# Peripheral_Connections.net
KiCad netlist of a schematic drawn in Altium Designer
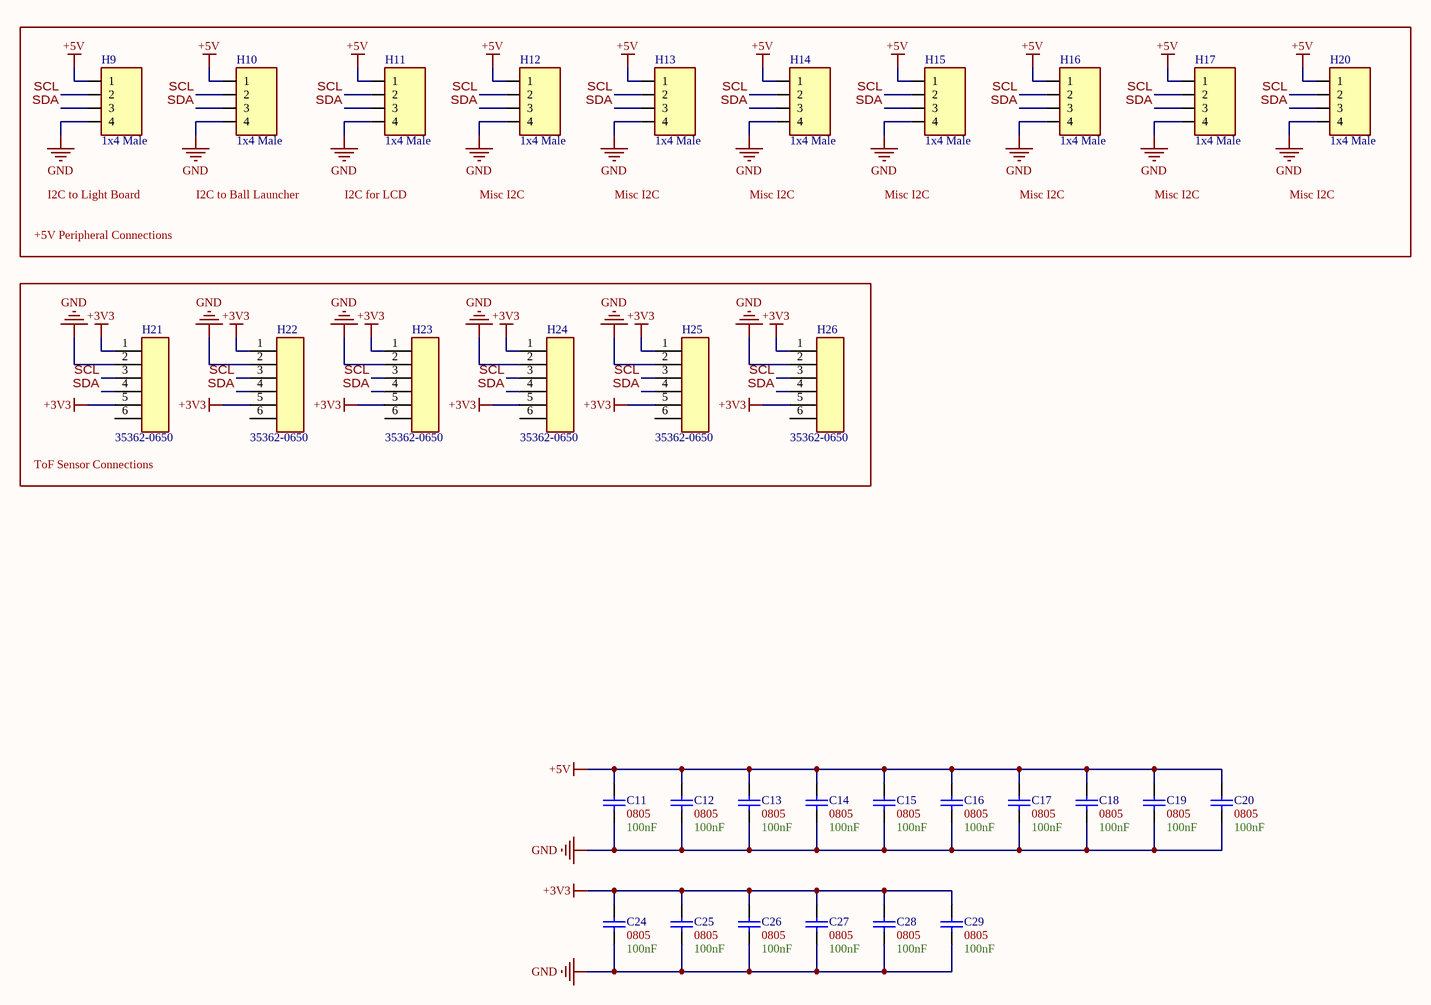
[diagram p0: Peripheral Connections.SchDoc]

(export (version "E")
  (design (tool "Eeschema 10.0.6"))
  (components
    (comp (ref "C11")
      (value "SMD Nonpolarized")
      (footprint "[Cap] SMD 0805")
      (fields (field (name "SIZE PACKAGE") "0805") (field (name "CAPACITANCE") "100nF"))
      (libsource (lib "RADM Components") (part "[Cap] SMD Nonpolarized"))
    )
    (comp (ref "C12")
      (value "SMD Nonpolarized")
      (footprint "[Cap] SMD 0805")
      (fields (field (name "SIZE PACKAGE") "0805") (field (name "CAPACITANCE") "100nF"))
      (libsource (lib "RADM Components") (part "[Cap] SMD Nonpolarized"))
    )
    (comp (ref "C13")
      (value "SMD Nonpolarized")
      (footprint "[Cap] SMD 0805")
      (fields (field (name "SIZE PACKAGE") "0805") (field (name "CAPACITANCE") "100nF"))
      (libsource (lib "RADM Components") (part "[Cap] SMD Nonpolarized"))
    )
    (comp (ref "C14")
      (value "SMD Nonpolarized")
      (footprint "[Cap] SMD 0805")
      (fields (field (name "SIZE PACKAGE") "0805") (field (name "CAPACITANCE") "100nF"))
      (libsource (lib "RADM Components") (part "[Cap] SMD Nonpolarized"))
    )
    (comp (ref "C15")
      (value "SMD Nonpolarized")
      (footprint "[Cap] SMD 0805")
      (fields (field (name "SIZE PACKAGE") "0805") (field (name "CAPACITANCE") "100nF"))
      (libsource (lib "RADM Components") (part "[Cap] SMD Nonpolarized"))
    )
    (comp (ref "C16")
      (value "SMD Nonpolarized")
      (footprint "[Cap] SMD 0805")
      (fields (field (name "SIZE PACKAGE") "0805") (field (name "CAPACITANCE") "100nF"))
      (libsource (lib "RADM Components") (part "[Cap] SMD Nonpolarized"))
    )
    (comp (ref "C17")
      (value "SMD Nonpolarized")
      (footprint "[Cap] SMD 0805")
      (fields (field (name "SIZE PACKAGE") "0805") (field (name "CAPACITANCE") "100nF"))
      (libsource (lib "RADM Components") (part "[Cap] SMD Nonpolarized"))
    )
    (comp (ref "C18")
      (value "SMD Nonpolarized")
      (footprint "[Cap] SMD 0805")
      (fields (field (name "SIZE PACKAGE") "0805") (field (name "CAPACITANCE") "100nF"))
      (libsource (lib "RADM Components") (part "[Cap] SMD Nonpolarized"))
    )
    (comp (ref "C19")
      (value "SMD Nonpolarized")
      (footprint "[Cap] SMD 0805")
      (fields (field (name "SIZE PACKAGE") "0805") (field (name "CAPACITANCE") "100nF"))
      (libsource (lib "RADM Components") (part "[Cap] SMD Nonpolarized"))
    )
    (comp (ref "C20")
      (value "SMD Nonpolarized")
      (footprint "[Cap] SMD 0805")
      (fields (field (name "SIZE PACKAGE") "0805") (field (name "CAPACITANCE") "100nF"))
      (libsource (lib "RADM Components") (part "[Cap] SMD Nonpolarized"))
    )
    (comp (ref "C24")
      (value "SMD Nonpolarized")
      (footprint "[Cap] SMD 0805")
      (fields (field (name "SIZE PACKAGE") "0805") (field (name "CAPACITANCE") "100nF"))
      (libsource (lib "RADM Components") (part "[Cap] SMD Nonpolarized"))
    )
    (comp (ref "C25")
      (value "SMD Nonpolarized")
      (footprint "[Cap] SMD 0805")
      (fields (field (name "SIZE PACKAGE") "0805") (field (name "CAPACITANCE") "100nF"))
      (libsource (lib "RADM Components") (part "[Cap] SMD Nonpolarized"))
    )
    (comp (ref "C26")
      (value "SMD Nonpolarized")
      (footprint "[Cap] SMD 0805")
      (fields (field (name "SIZE PACKAGE") "0805") (field (name "CAPACITANCE") "100nF"))
      (libsource (lib "RADM Components") (part "[Cap] SMD Nonpolarized"))
    )
    (comp (ref "C27")
      (value "SMD Nonpolarized")
      (footprint "[Cap] SMD 0805")
      (fields (field (name "SIZE PACKAGE") "0805") (field (name "CAPACITANCE") "100nF"))
      (libsource (lib "RADM Components") (part "[Cap] SMD Nonpolarized"))
    )
    (comp (ref "C28")
      (value "SMD Nonpolarized")
      (footprint "[Cap] SMD 0805")
      (fields (field (name "SIZE PACKAGE") "0805") (field (name "CAPACITANCE") "100nF"))
      (libsource (lib "RADM Components") (part "[Cap] SMD Nonpolarized"))
    )
    (comp (ref "C29")
      (value "SMD Nonpolarized")
      (footprint "[Cap] SMD 0805")
      (fields (field (name "SIZE PACKAGE") "0805") (field (name "CAPACITANCE") "100nF"))
      (libsource (lib "RADM Components") (part "[Cap] SMD Nonpolarized"))
    )
    (comp (ref "H9")
      (value "1x4 Male")
      (footprint "[Header] Shrouded 1x4 Male")
      (description "70543-0003\r\nMates with 0050579404")
      (libsource (lib "RADM Connectors") (part "[Header] Shrouded 1x4 Male"))
    )
    (comp (ref "H10")
      (value "1x4 Male")
      (footprint "[Header] Shrouded 1x4 Male")
      (description "70543-0003\r\nMates with 0050579404")
      (libsource (lib "RADM Connectors") (part "[Header] Shrouded 1x4 Male"))
    )
    (comp (ref "H11")
      (value "1x4 Male")
      (footprint "[Header] Shrouded 1x4 Male")
      (description "70543-0003\r\nMates with 0050579404")
      (libsource (lib "RADM Connectors") (part "[Header] Shrouded 1x4 Male"))
    )
    (comp (ref "H12")
      (value "1x4 Male")
      (footprint "[Header] Shrouded 1x4 Male")
      (description "70543-0003\r\nMates with 0050579404")
      (libsource (lib "RADM Connectors") (part "[Header] Shrouded 1x4 Male"))
    )
    (comp (ref "H13")
      (value "1x4 Male")
      (footprint "[Header] Shrouded 1x4 Male")
      (description "70543-0003\r\nMates with 0050579404")
      (libsource (lib "RADM Connectors") (part "[Header] Shrouded 1x4 Male"))
    )
    (comp (ref "H14")
      (value "1x4 Male")
      (footprint "[Header] Shrouded 1x4 Male")
      (description "70543-0003\r\nMates with 0050579404")
      (libsource (lib "RADM Connectors") (part "[Header] Shrouded 1x4 Male"))
    )
    (comp (ref "H15")
      (value "1x4 Male")
      (footprint "[Header] Shrouded 1x4 Male")
      (description "70543-0003\r\nMates with 0050579404")
      (libsource (lib "RADM Connectors") (part "[Header] Shrouded 1x4 Male"))
    )
    (comp (ref "H16")
      (value "1x4 Male")
      (footprint "[Header] Shrouded 1x4 Male")
      (description "70543-0003\r\nMates with 0050579404")
      (libsource (lib "RADM Connectors") (part "[Header] Shrouded 1x4 Male"))
    )
    (comp (ref "H17")
      (value "1x4 Male")
      (footprint "[Header] Shrouded 1x4 Male")
      (description "70543-0003\r\nMates with 0050579404")
      (libsource (lib "RADM Connectors") (part "[Header] Shrouded 1x4 Male"))
    )
    (comp (ref "H20")
      (value "1x4 Male")
      (footprint "[Header] Shrouded 1x4 Male")
      (description "70543-0003\r\nMates with 0050579404")
      (libsource (lib "RADM Connectors") (part "[Header] Shrouded 1x4 Male"))
    )
    (comp (ref "H21")
      (value "35362-0650")
      (footprint "[Sherlock] 6pin")
      (description "2.00mm pitch")
      (libsource (lib "RADM Connectors") (part "[Sherlock] 6pin"))
    )
    (comp (ref "H22")
      (value "35362-0650")
      (footprint "[Sherlock] 6pin")
      (description "2.00mm pitch")
      (libsource (lib "RADM Connectors") (part "[Sherlock] 6pin"))
    )
    (comp (ref "H23")
      (value "35362-0650")
      (footprint "[Sherlock] 6pin")
      (description "2.00mm pitch")
      (libsource (lib "RADM Connectors") (part "[Sherlock] 6pin"))
    )
    (comp (ref "H24")
      (value "35362-0650")
      (footprint "[Sherlock] 6pin")
      (description "2.00mm pitch")
      (libsource (lib "RADM Connectors") (part "[Sherlock] 6pin"))
    )
    (comp (ref "H25")
      (value "35362-0650")
      (footprint "[Sherlock] 6pin")
      (description "2.00mm pitch")
      (libsource (lib "RADM Connectors") (part "[Sherlock] 6pin"))
    )
    (comp (ref "H26")
      (value "35362-0650")
      (footprint "[Sherlock] 6pin")
      (description "2.00mm pitch")
      (libsource (lib "RADM Connectors") (part "[Sherlock] 6pin"))
    )
  )
  (nets
    (net (code "1") (name "+3V3") (class "Default")
      (node (ref "C24") (pin "2") (pinfunction "2_2") (pintype "passive"))
      (node (ref "C25") (pin "2") (pinfunction "2_2") (pintype "passive"))
      (node (ref "C26") (pin "2") (pinfunction "2_2") (pintype "passive"))
      (node (ref "C27") (pin "2") (pinfunction "2_2") (pintype "passive"))
      (node (ref "C28") (pin "2") (pinfunction "2_2") (pintype "passive"))
      (node (ref "C29") (pin "2") (pinfunction "2_2") (pintype "passive"))
      (node (ref "H21") (pin "1") (pinfunction "1_1") (pintype "passive"))
      (node (ref "H21") (pin "5") (pinfunction "5_5") (pintype "passive"))
      (node (ref "H22") (pin "1") (pinfunction "1_1") (pintype "passive"))
      (node (ref "H22") (pin "5") (pinfunction "5_5") (pintype "passive"))
      (node (ref "H23") (pin "1") (pinfunction "1_1") (pintype "passive"))
      (node (ref "H23") (pin "5") (pinfunction "5_5") (pintype "passive"))
      (node (ref "H24") (pin "1") (pinfunction "1_1") (pintype "passive"))
      (node (ref "H24") (pin "5") (pinfunction "5_5") (pintype "passive"))
      (node (ref "H25") (pin "1") (pinfunction "1_1") (pintype "passive"))
      (node (ref "H25") (pin "5") (pinfunction "5_5") (pintype "passive"))
      (node (ref "H26") (pin "1") (pinfunction "1_1") (pintype "passive"))
      (node (ref "H26") (pin "5") (pinfunction "5_5") (pintype "passive"))
    )
    (net (code "2") (name "+5V") (class "Default")
      (node (ref "C11") (pin "2") (pinfunction "2_2") (pintype "passive"))
      (node (ref "C12") (pin "2") (pinfunction "2_2") (pintype "passive"))
      (node (ref "C13") (pin "2") (pinfunction "2_2") (pintype "passive"))
      (node (ref "C14") (pin "2") (pinfunction "2_2") (pintype "passive"))
      (node (ref "C15") (pin "2") (pinfunction "2_2") (pintype "passive"))
      (node (ref "C16") (pin "2") (pinfunction "2_2") (pintype "passive"))
      (node (ref "C17") (pin "2") (pinfunction "2_2") (pintype "passive"))
      (node (ref "C18") (pin "2") (pinfunction "2_2") (pintype "passive"))
      (node (ref "C19") (pin "2") (pinfunction "2_2") (pintype "passive"))
      (node (ref "C20") (pin "2") (pinfunction "2_2") (pintype "passive"))
      (node (ref "H10") (pin "1") (pinfunction "1_1") (pintype "passive"))
      (node (ref "H11") (pin "1") (pinfunction "1_1") (pintype "passive"))
      (node (ref "H12") (pin "1") (pinfunction "1_1") (pintype "passive"))
      (node (ref "H13") (pin "1") (pinfunction "1_1") (pintype "passive"))
      (node (ref "H14") (pin "1") (pinfunction "1_1") (pintype "passive"))
      (node (ref "H15") (pin "1") (pinfunction "1_1") (pintype "passive"))
      (node (ref "H16") (pin "1") (pinfunction "1_1") (pintype "passive"))
      (node (ref "H17") (pin "1") (pinfunction "1_1") (pintype "passive"))
      (node (ref "H20") (pin "1") (pinfunction "1_1") (pintype "passive"))
      (node (ref "H9") (pin "1") (pinfunction "1_1") (pintype "passive"))
    )
    (net (code "3") (name "/SCL") (class "Default")
      (node (ref "H10") (pin "2") (pinfunction "2_2") (pintype "passive"))
      (node (ref "H11") (pin "2") (pinfunction "2_2") (pintype "passive"))
      (node (ref "H12") (pin "2") (pinfunction "2_2") (pintype "passive"))
      (node (ref "H13") (pin "2") (pinfunction "2_2") (pintype "passive"))
      (node (ref "H14") (pin "2") (pinfunction "2_2") (pintype "passive"))
      (node (ref "H15") (pin "2") (pinfunction "2_2") (pintype "passive"))
      (node (ref "H16") (pin "2") (pinfunction "2_2") (pintype "passive"))
      (node (ref "H17") (pin "2") (pinfunction "2_2") (pintype "passive"))
      (node (ref "H20") (pin "2") (pinfunction "2_2") (pintype "passive"))
      (node (ref "H21") (pin "3") (pinfunction "3_3") (pintype "passive"))
      (node (ref "H22") (pin "3") (pinfunction "3_3") (pintype "passive"))
      (node (ref "H23") (pin "3") (pinfunction "3_3") (pintype "passive"))
      (node (ref "H24") (pin "3") (pinfunction "3_3") (pintype "passive"))
      (node (ref "H25") (pin "3") (pinfunction "3_3") (pintype "passive"))
      (node (ref "H26") (pin "3") (pinfunction "3_3") (pintype "passive"))
      (node (ref "H9") (pin "2") (pinfunction "2_2") (pintype "passive"))
    )
    (net (code "4") (name "/SDA") (class "Default")
      (node (ref "H10") (pin "3") (pinfunction "3_3") (pintype "passive"))
      (node (ref "H11") (pin "3") (pinfunction "3_3") (pintype "passive"))
      (node (ref "H12") (pin "3") (pinfunction "3_3") (pintype "passive"))
      (node (ref "H13") (pin "3") (pinfunction "3_3") (pintype "passive"))
      (node (ref "H14") (pin "3") (pinfunction "3_3") (pintype "passive"))
      (node (ref "H15") (pin "3") (pinfunction "3_3") (pintype "passive"))
      (node (ref "H16") (pin "3") (pinfunction "3_3") (pintype "passive"))
      (node (ref "H17") (pin "3") (pinfunction "3_3") (pintype "passive"))
      (node (ref "H20") (pin "3") (pinfunction "3_3") (pintype "passive"))
      (node (ref "H21") (pin "4") (pinfunction "4_4") (pintype "passive"))
      (node (ref "H22") (pin "4") (pinfunction "4_4") (pintype "passive"))
      (node (ref "H23") (pin "4") (pinfunction "4_4") (pintype "passive"))
      (node (ref "H24") (pin "4") (pinfunction "4_4") (pintype "passive"))
      (node (ref "H25") (pin "4") (pinfunction "4_4") (pintype "passive"))
      (node (ref "H26") (pin "4") (pinfunction "4_4") (pintype "passive"))
      (node (ref "H9") (pin "3") (pinfunction "3_3") (pintype "passive"))
    )
    (net (code "5") (name "GND") (class "Default")
      (node (ref "C11") (pin "1") (pinfunction "1_1") (pintype "passive"))
      (node (ref "C12") (pin "1") (pinfunction "1_1") (pintype "passive"))
      (node (ref "C13") (pin "1") (pinfunction "1_1") (pintype "passive"))
      (node (ref "C14") (pin "1") (pinfunction "1_1") (pintype "passive"))
      (node (ref "C15") (pin "1") (pinfunction "1_1") (pintype "passive"))
      (node (ref "C16") (pin "1") (pinfunction "1_1") (pintype "passive"))
      (node (ref "C17") (pin "1") (pinfunction "1_1") (pintype "passive"))
      (node (ref "C18") (pin "1") (pinfunction "1_1") (pintype "passive"))
      (node (ref "C19") (pin "1") (pinfunction "1_1") (pintype "passive"))
      (node (ref "C20") (pin "1") (pinfunction "1_1") (pintype "passive"))
      (node (ref "C24") (pin "1") (pinfunction "1_1") (pintype "passive"))
      (node (ref "C25") (pin "1") (pinfunction "1_1") (pintype "passive"))
      (node (ref "C26") (pin "1") (pinfunction "1_1") (pintype "passive"))
      (node (ref "C27") (pin "1") (pinfunction "1_1") (pintype "passive"))
      (node (ref "C28") (pin "1") (pinfunction "1_1") (pintype "passive"))
      (node (ref "C29") (pin "1") (pinfunction "1_1") (pintype "passive"))
      (node (ref "H10") (pin "4") (pinfunction "4_4") (pintype "passive"))
      (node (ref "H11") (pin "4") (pinfunction "4_4") (pintype "passive"))
      (node (ref "H12") (pin "4") (pinfunction "4_4") (pintype "passive"))
      (node (ref "H13") (pin "4") (pinfunction "4_4") (pintype "passive"))
      (node (ref "H14") (pin "4") (pinfunction "4_4") (pintype "passive"))
      (node (ref "H15") (pin "4") (pinfunction "4_4") (pintype "passive"))
      (node (ref "H16") (pin "4") (pinfunction "4_4") (pintype "passive"))
      (node (ref "H17") (pin "4") (pinfunction "4_4") (pintype "passive"))
      (node (ref "H20") (pin "4") (pinfunction "4_4") (pintype "passive"))
      (node (ref "H21") (pin "2") (pinfunction "2_2") (pintype "passive"))
      (node (ref "H22") (pin "2") (pinfunction "2_2") (pintype "passive"))
      (node (ref "H23") (pin "2") (pinfunction "2_2") (pintype "passive"))
      (node (ref "H24") (pin "2") (pinfunction "2_2") (pintype "passive"))
      (node (ref "H25") (pin "2") (pinfunction "2_2") (pintype "passive"))
      (node (ref "H26") (pin "2") (pinfunction "2_2") (pintype "passive"))
      (node (ref "H9") (pin "4") (pinfunction "4_4") (pintype "passive"))
    )
    (net (code "6") (name "unconnected-(H21-Pad6)") (class "Default")
      (node (ref "H21") (pin "6") (pinfunction "6_6") (pintype "passive"))
    )
    (net (code "7") (name "unconnected-(H22-Pad6)") (class "Default")
      (node (ref "H22") (pin "6") (pinfunction "6_6") (pintype "passive"))
    )
    (net (code "8") (name "unconnected-(H23-Pad6)") (class "Default")
      (node (ref "H23") (pin "6") (pinfunction "6_6") (pintype "passive"))
    )
    (net (code "9") (name "unconnected-(H24-Pad6)") (class "Default")
      (node (ref "H24") (pin "6") (pinfunction "6_6") (pintype "passive"))
    )
    (net (code "10") (name "unconnected-(H25-Pad6)") (class "Default")
      (node (ref "H25") (pin "6") (pinfunction "6_6") (pintype "passive"))
    )
    (net (code "11") (name "unconnected-(H26-Pad6)") (class "Default")
      (node (ref "H26") (pin "6") (pinfunction "6_6") (pintype "passive"))
    )
  )
)
